# rn4020_adapter.net
KiCad netlist of a schematic drawn in EAGLE
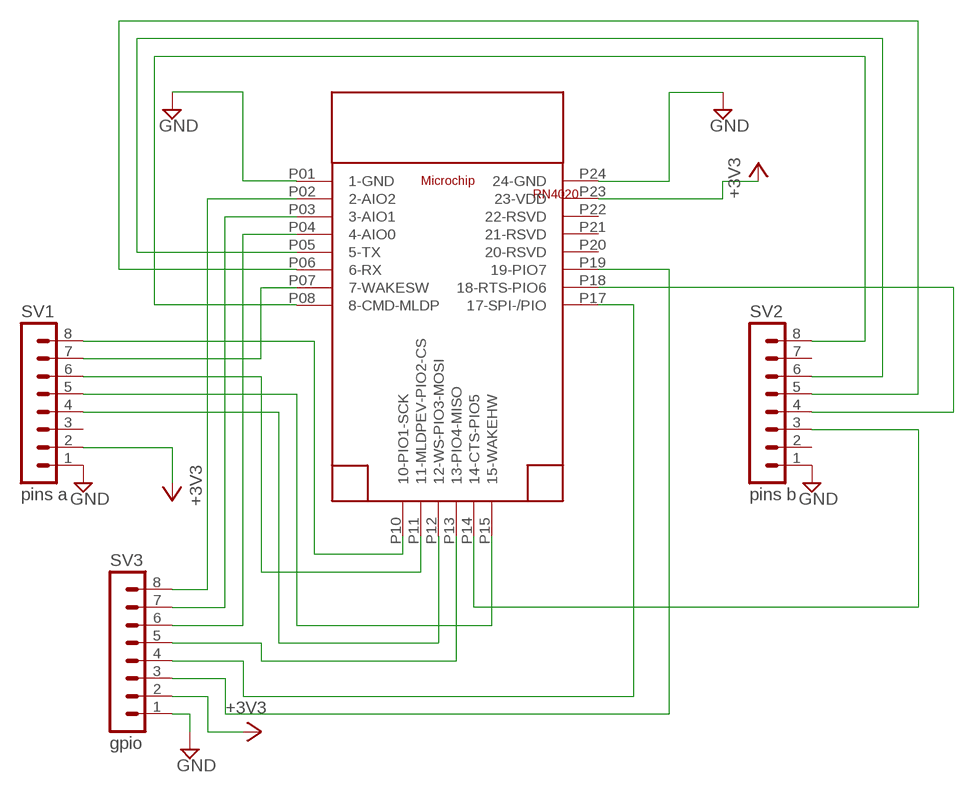
[diagram p0: schematic, sheet 1]

(export (version "E")
  (design (tool "Eeschema 10.0.6"))
  (components
    (comp (ref "SV1")
      (value "pins a")
      (footprint "eagle-import:MA08-1")
      (libsource (lib "eagle-import") (part "MA08-1"))
    )
    (comp (ref "SV2")
      (value "pins b")
      (footprint "eagle-import:MA08-1")
      (libsource (lib "eagle-import") (part "MA08-1"))
    )
    (comp (ref "SV3")
      (value "gpio")
      (footprint "eagle-import:MA08-1")
      (libsource (lib "eagle-import") (part "MA08-1"))
    )
    (comp (ref "U$1")
      (value "RN4020")
      (footprint "eagle-import:RN4020SMD")
      (libsource (lib "eagle-import") (part "RN4020"))
    )
  )
  (nets
    (net (code "1") (name "+3V3") (class "Default")
      (node (ref "SV1") (pin "2") (pinfunction "2_2") (pintype "passive"))
      (node (ref "SV3") (pin "2") (pinfunction "2_2") (pintype "passive"))
      (node (ref "U$1") (pin "P23") (pinfunction "23-VDD_P23") (pintype "bidirectional"))
    )
    (net (code "2") (name "GND") (class "Default")
      (node (ref "SV1") (pin "1") (pinfunction "1_1") (pintype "passive"))
      (node (ref "SV2") (pin "1") (pinfunction "1_1") (pintype "passive"))
      (node (ref "SV3") (pin "1") (pinfunction "1_1") (pintype "passive"))
      (node (ref "U$1") (pin "P01") (pinfunction "1-GND_P01") (pintype "bidirectional"))
      (node (ref "U$1") (pin "P24") (pinfunction "24-GND_P24") (pintype "bidirectional"))
    )
    (net (code "3") (name "Net-(U$1-2-AIO2)") (class "Default")
      (node (ref "SV3") (pin "8") (pinfunction "8_8") (pintype "passive"))
      (node (ref "U$1") (pin "P02") (pinfunction "2-AIO2_P02") (pintype "bidirectional"))
    )
    (net (code "4") (name "Net-(U$1-3-AIO1)") (class "Default")
      (node (ref "SV3") (pin "7") (pinfunction "7_7") (pintype "passive"))
      (node (ref "U$1") (pin "P03") (pinfunction "3-AIO1_P03") (pintype "bidirectional"))
    )
    (net (code "5") (name "Net-(U$1-4-AIO0)") (class "Default")
      (node (ref "SV3") (pin "6") (pinfunction "6_6") (pintype "passive"))
      (node (ref "U$1") (pin "P04") (pinfunction "4-AIO0_P04") (pintype "bidirectional"))
    )
    (net (code "6") (name "Net-(U$1-5-TX)") (class "Default")
      (node (ref "SV2") (pin "6") (pinfunction "6_6") (pintype "passive"))
      (node (ref "U$1") (pin "P05") (pinfunction "5-TX_P05") (pintype "bidirectional"))
    )
    (net (code "7") (name "Net-(U$1-6-RX)") (class "Default")
      (node (ref "SV2") (pin "5") (pinfunction "5_5") (pintype "passive"))
      (node (ref "U$1") (pin "P06") (pinfunction "6-RX_P06") (pintype "bidirectional"))
    )
    (net (code "8") (name "Net-(U$1-7-WAKESW)") (class "Default")
      (node (ref "SV1") (pin "7") (pinfunction "7_7") (pintype "passive"))
      (node (ref "U$1") (pin "P07") (pinfunction "7-WAKESW_P07") (pintype "bidirectional"))
    )
    (net (code "9") (name "Net-(U$1-8-CMD-MLDP)") (class "Default")
      (node (ref "SV2") (pin "8") (pinfunction "8_8") (pintype "passive"))
      (node (ref "U$1") (pin "P08") (pinfunction "8-CMD-MLDP_P08") (pintype "bidirectional"))
    )
    (net (code "10") (name "Net-(U$1-10-PIO1-SCK)") (class "Default")
      (node (ref "SV1") (pin "8") (pinfunction "8_8") (pintype "passive"))
      (node (ref "U$1") (pin "P10") (pinfunction "10-PIO1-SCK_P10") (pintype "bidirectional"))
    )
    (net (code "11") (name "Net-(U$1-11-MLDPEV-PIO2-CS)") (class "Default")
      (node (ref "SV1") (pin "6") (pinfunction "6_6") (pintype "passive"))
      (node (ref "U$1") (pin "P11") (pinfunction "11-MLDPEV-PIO2-CS_P11") (pintype "bidirectional"))
    )
    (net (code "12") (name "Net-(U$1-12-WS-PIO3-MOSI)") (class "Default")
      (node (ref "SV1") (pin "4") (pinfunction "4_4") (pintype "passive"))
      (node (ref "U$1") (pin "P12") (pinfunction "12-WS-PIO3-MOSI_P12") (pintype "bidirectional"))
    )
    (net (code "13") (name "Net-(U$1-13-PIO4-MISO)") (class "Default")
      (node (ref "SV3") (pin "5") (pinfunction "5_5") (pintype "passive"))
      (node (ref "U$1") (pin "P13") (pinfunction "13-PIO4-MISO_P13") (pintype "bidirectional"))
    )
    (net (code "14") (name "Net-(U$1-14-CTS-PIO5)") (class "Default")
      (node (ref "SV2") (pin "3") (pinfunction "3_3") (pintype "passive"))
      (node (ref "U$1") (pin "P14") (pinfunction "14-CTS-PIO5_P14") (pintype "bidirectional"))
    )
    (net (code "15") (name "Net-(U$1-15-WAKEHW)") (class "Default")
      (node (ref "SV1") (pin "5") (pinfunction "5_5") (pintype "passive"))
      (node (ref "U$1") (pin "P15") (pinfunction "15-WAKEHW_P15") (pintype "bidirectional"))
    )
    (net (code "16") (name "Net-(U$1-17-SPI-{slash}PIO)") (class "Default")
      (node (ref "SV3") (pin "4") (pinfunction "4_4") (pintype "passive"))
      (node (ref "U$1") (pin "P17") (pinfunction "17-SPI-/PIO_P17") (pintype "bidirectional"))
    )
    (net (code "17") (name "Net-(U$1-18-RTS-PIO6)") (class "Default")
      (node (ref "SV2") (pin "4") (pinfunction "4_4") (pintype "passive"))
      (node (ref "U$1") (pin "P18") (pinfunction "18-RTS-PIO6_P18") (pintype "bidirectional"))
    )
    (net (code "18") (name "Net-(U$1-19-PIO7)") (class "Default")
      (node (ref "SV3") (pin "3") (pinfunction "3_3") (pintype "passive"))
      (node (ref "U$1") (pin "P19") (pinfunction "19-PIO7_P19") (pintype "bidirectional"))
    )
    (net (code "19") (name "unconnected-(SV1-Pad3)") (class "Default")
      (node (ref "SV1") (pin "3") (pinfunction "3_3") (pintype "passive"))
    )
    (net (code "20") (name "unconnected-(SV2-Pad2)") (class "Default")
      (node (ref "SV2") (pin "2") (pinfunction "2_2") (pintype "passive"))
    )
    (net (code "21") (name "unconnected-(SV2-Pad7)") (class "Default")
      (node (ref "SV2") (pin "7") (pinfunction "7_7") (pintype "passive"))
    )
    (net (code "22") (name "unconnected-(U$1-20-RSVD-PadP20)") (class "Default")
      (node (ref "U$1") (pin "P20") (pinfunction "20-RSVD_P20") (pintype "bidirectional"))
    )
    (net (code "23") (name "unconnected-(U$1-21-RSVD-PadP21)") (class "Default")
      (node (ref "U$1") (pin "P21") (pinfunction "21-RSVD_P21") (pintype "bidirectional"))
    )
    (net (code "24") (name "unconnected-(U$1-22-RSVD-PadP22)") (class "Default")
      (node (ref "U$1") (pin "P22") (pinfunction "22-RSVD_P22") (pintype "bidirectional"))
    )
  )
)
